# SENSE.net
KiCad netlist of a schematic drawn in Altium Designer
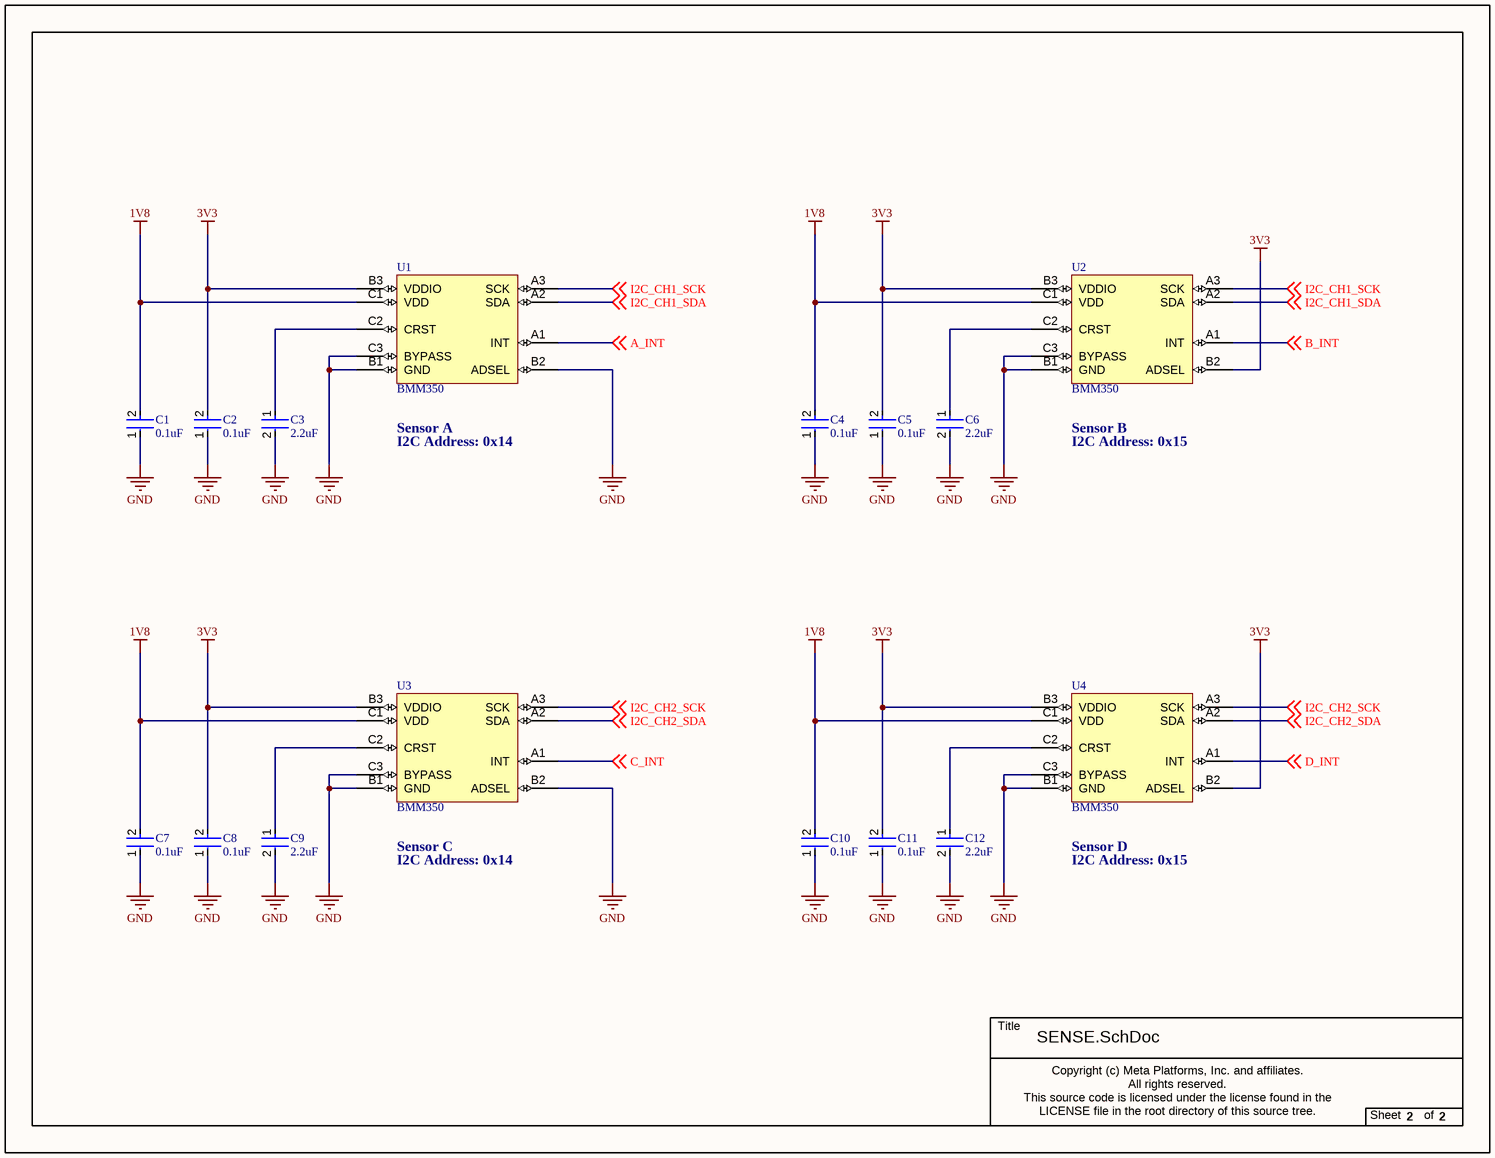
[diagram p0: SENSE.SchDoc]

(export (version "E")
  (design (tool "Eeschema 10.0.6"))
  (components
    (comp (ref "C1")
      (value "0.1uF")
      (footprint "FP-GRM15-MFG")
      (description "CAP CER 0.1UF 16V X7R 0402")
      (fields (field (name "MANUFACTURER PART NUMBER") "GRM155R71C104KA88D") (field (name "TOLERANCE") "10%"))
      (libsource (lib "Altium Content Vault") (part "236180d848d6139a670b325ea6854c9"))
    )
    (comp (ref "C2")
      (value "0.1uF")
      (footprint "FP-GRM15-MFG")
      (description "CAP CER 0.1UF 16V X7R 0402")
      (fields (field (name "MANUFACTURER PART NUMBER") "GRM155R71C104KA88D") (field (name "TOLERANCE") "10%"))
      (libsource (lib "Altium Content Vault") (part "236180d848d6139a670b325ea6854c9"))
    )
    (comp (ref "C3")
      (value "2.2uF")
      (footprint "FP-C1005-050-0_15-0_1-MFG")
      (description "CAP CER 2.2UF 10V X7S 0402")
      (fields (field (name "TOLERANCE") "10%"))
      (libsource (lib "Altium Content Vault") (part "b4654b650e69147ec39a6b967a45e02"))
    )
    (comp (ref "C4")
      (value "0.1uF")
      (footprint "FP-GRM15-MFG")
      (description "CAP CER 0.1UF 16V X7R 0402")
      (fields (field (name "MANUFACTURER PART NUMBER") "GRM155R71C104KA88D") (field (name "TOLERANCE") "10%"))
      (libsource (lib "Altium Content Vault") (part "236180d848d6139a670b325ea6854c9"))
    )
    (comp (ref "C5")
      (value "0.1uF")
      (footprint "FP-GRM15-MFG")
      (description "CAP CER 0.1UF 16V X7R 0402")
      (fields (field (name "MANUFACTURER PART NUMBER") "GRM155R71C104KA88D") (field (name "TOLERANCE") "10%"))
      (libsource (lib "Altium Content Vault") (part "236180d848d6139a670b325ea6854c9"))
    )
    (comp (ref "C6")
      (value "2.2uF")
      (footprint "FP-C1005-050-0_15-0_1-MFG")
      (description "CAP CER 2.2UF 10V X7S 0402")
      (fields (field (name "TOLERANCE") "10%"))
      (libsource (lib "Altium Content Vault") (part "b4654b650e69147ec39a6b967a45e02"))
    )
    (comp (ref "C7")
      (value "0.1uF")
      (footprint "FP-GRM15-MFG")
      (description "CAP CER 0.1UF 16V X7R 0402")
      (fields (field (name "MANUFACTURER PART NUMBER") "GRM155R71C104KA88D") (field (name "TOLERANCE") "10%"))
      (libsource (lib "Altium Content Vault") (part "236180d848d6139a670b325ea6854c9"))
    )
    (comp (ref "C8")
      (value "0.1uF")
      (footprint "FP-GRM15-MFG")
      (description "CAP CER 0.1UF 16V X7R 0402")
      (fields (field (name "MANUFACTURER PART NUMBER") "GRM155R71C104KA88D") (field (name "TOLERANCE") "10%"))
      (libsource (lib "Altium Content Vault") (part "236180d848d6139a670b325ea6854c9"))
    )
    (comp (ref "C9")
      (value "2.2uF")
      (footprint "FP-C1005-050-0_15-0_1-MFG")
      (description "CAP CER 2.2UF 10V X7S 0402")
      (fields (field (name "TOLERANCE") "10%"))
      (libsource (lib "Altium Content Vault") (part "b4654b650e69147ec39a6b967a45e02"))
    )
    (comp (ref "C10")
      (value "0.1uF")
      (footprint "FP-GRM15-MFG")
      (description "CAP CER 0.1UF 16V X7R 0402")
      (fields (field (name "MANUFACTURER PART NUMBER") "GRM155R71C104KA88D") (field (name "TOLERANCE") "10%"))
      (libsource (lib "Altium Content Vault") (part "236180d848d6139a670b325ea6854c9"))
    )
    (comp (ref "C11")
      (value "0.1uF")
      (footprint "FP-GRM15-MFG")
      (description "CAP CER 0.1UF 16V X7R 0402")
      (fields (field (name "MANUFACTURER PART NUMBER") "GRM155R71C104KA88D") (field (name "TOLERANCE") "10%"))
      (libsource (lib "Altium Content Vault") (part "236180d848d6139a670b325ea6854c9"))
    )
    (comp (ref "C12")
      (value "2.2uF")
      (footprint "FP-C1005-050-0_15-0_1-MFG")
      (description "CAP CER 2.2UF 10V X7S 0402")
      (fields (field (name "TOLERANCE") "10%"))
      (libsource (lib "Altium Content Vault") (part "b4654b650e69147ec39a6b967a45e02"))
    )
    (comp (ref "U1") (value "BMM350") (footprint "BMM350") (libsource (lib "bmm350") (part "BMM350")))
    (comp (ref "U2") (value "BMM350") (footprint "BMM350") (libsource (lib "bmm350") (part "BMM350")))
    (comp (ref "U3") (value "BMM350") (footprint "BMM350") (libsource (lib "bmm350") (part "BMM350")))
    (comp (ref "U4") (value "BMM350") (footprint "BMM350") (libsource (lib "bmm350") (part "BMM350")))
  )
  (nets
    (net (code "1") (name "1V8") (class "Default")
      (node (ref "C1") (pin "2") (pinfunction "2_2") (pintype "passive"))
      (node (ref "C10") (pin "2") (pinfunction "2_2") (pintype "passive"))
      (node (ref "C4") (pin "2") (pinfunction "2_2") (pintype "passive"))
      (node (ref "C7") (pin "2") (pinfunction "2_2") (pintype "passive"))
      (node (ref "U1") (pin "C1") (pinfunction "VDD_C1") (pintype "bidirectional"))
      (node (ref "U2") (pin "C1") (pinfunction "VDD_C1") (pintype "bidirectional"))
      (node (ref "U3") (pin "C1") (pinfunction "VDD_C1") (pintype "bidirectional"))
      (node (ref "U4") (pin "C1") (pinfunction "VDD_C1") (pintype "bidirectional"))
    )
    (net (code "2") (name "3V3") (class "Default")
      (node (ref "C11") (pin "2") (pinfunction "2_2") (pintype "passive"))
      (node (ref "C2") (pin "2") (pinfunction "2_2") (pintype "passive"))
      (node (ref "C5") (pin "2") (pinfunction "2_2") (pintype "passive"))
      (node (ref "C8") (pin "2") (pinfunction "2_2") (pintype "passive"))
      (node (ref "U1") (pin "B3") (pinfunction "VDDIO_B3") (pintype "bidirectional"))
      (node (ref "U2") (pin "B2") (pinfunction "ADSEL_B2") (pintype "bidirectional"))
      (node (ref "U2") (pin "B3") (pinfunction "VDDIO_B3") (pintype "bidirectional"))
      (node (ref "U3") (pin "B3") (pinfunction "VDDIO_B3") (pintype "bidirectional"))
      (node (ref "U4") (pin "B2") (pinfunction "ADSEL_B2") (pintype "bidirectional"))
      (node (ref "U4") (pin "B3") (pinfunction "VDDIO_B3") (pintype "bidirectional"))
    )
    (net (code "3") (name "A_INT") (class "Default")
      (node (ref "U1") (pin "A1") (pinfunction "INT_A1") (pintype "bidirectional"))
    )
    (net (code "4") (name "B_INT") (class "Default")
      (node (ref "U2") (pin "A1") (pinfunction "INT_A1") (pintype "bidirectional"))
    )
    (net (code "5") (name "C_INT") (class "Default")
      (node (ref "U3") (pin "A1") (pinfunction "INT_A1") (pintype "bidirectional"))
    )
    (net (code "6") (name "D_INT") (class "Default")
      (node (ref "U4") (pin "A1") (pinfunction "INT_A1") (pintype "bidirectional"))
    )
    (net (code "7") (name "GND") (class "Default")
      (node (ref "C1") (pin "1") (pinfunction "1_1") (pintype "passive"))
      (node (ref "C10") (pin "1") (pinfunction "1_1") (pintype "passive"))
      (node (ref "C11") (pin "1") (pinfunction "1_1") (pintype "passive"))
      (node (ref "C12") (pin "2") (pinfunction "2_2") (pintype "passive"))
      (node (ref "C2") (pin "1") (pinfunction "1_1") (pintype "passive"))
      (node (ref "C3") (pin "2") (pinfunction "2_2") (pintype "passive"))
      (node (ref "C4") (pin "1") (pinfunction "1_1") (pintype "passive"))
      (node (ref "C5") (pin "1") (pinfunction "1_1") (pintype "passive"))
      (node (ref "C6") (pin "2") (pinfunction "2_2") (pintype "passive"))
      (node (ref "C7") (pin "1") (pinfunction "1_1") (pintype "passive"))
      (node (ref "C8") (pin "1") (pinfunction "1_1") (pintype "passive"))
      (node (ref "C9") (pin "2") (pinfunction "2_2") (pintype "passive"))
      (node (ref "U1") (pin "B1") (pinfunction "GND_B1") (pintype "bidirectional"))
      (node (ref "U1") (pin "B2") (pinfunction "ADSEL_B2") (pintype "bidirectional"))
      (node (ref "U1") (pin "C3") (pinfunction "BYPASS_C3") (pintype "bidirectional"))
      (node (ref "U2") (pin "B1") (pinfunction "GND_B1") (pintype "bidirectional"))
      (node (ref "U2") (pin "C3") (pinfunction "BYPASS_C3") (pintype "bidirectional"))
      (node (ref "U3") (pin "B1") (pinfunction "GND_B1") (pintype "bidirectional"))
      (node (ref "U3") (pin "B2") (pinfunction "ADSEL_B2") (pintype "bidirectional"))
      (node (ref "U3") (pin "C3") (pinfunction "BYPASS_C3") (pintype "bidirectional"))
      (node (ref "U4") (pin "B1") (pinfunction "GND_B1") (pintype "bidirectional"))
      (node (ref "U4") (pin "C3") (pinfunction "BYPASS_C3") (pintype "bidirectional"))
    )
    (net (code "8") (name "I2C_CH1_SCK") (class "Default")
      (node (ref "U1") (pin "A3") (pinfunction "SCK_A3") (pintype "bidirectional"))
      (node (ref "U2") (pin "A3") (pinfunction "SCK_A3") (pintype "bidirectional"))
    )
    (net (code "9") (name "I2C_CH1_SDA") (class "Default")
      (node (ref "U1") (pin "A2") (pinfunction "SDA_A2") (pintype "bidirectional"))
      (node (ref "U2") (pin "A2") (pinfunction "SDA_A2") (pintype "bidirectional"))
    )
    (net (code "10") (name "I2C_CH2_SCK") (class "Default")
      (node (ref "U3") (pin "A3") (pinfunction "SCK_A3") (pintype "bidirectional"))
      (node (ref "U4") (pin "A3") (pinfunction "SCK_A3") (pintype "bidirectional"))
    )
    (net (code "11") (name "I2C_CH2_SDA") (class "Default")
      (node (ref "U3") (pin "A2") (pinfunction "SDA_A2") (pintype "bidirectional"))
      (node (ref "U4") (pin "A2") (pinfunction "SDA_A2") (pintype "bidirectional"))
    )
    (net (code "12") (name "Net-(U1-CRST)") (class "Default")
      (node (ref "C3") (pin "1") (pinfunction "1_1") (pintype "passive"))
      (node (ref "U1") (pin "C2") (pinfunction "CRST_C2") (pintype "bidirectional"))
    )
    (net (code "13") (name "Net-(U2-CRST)") (class "Default")
      (node (ref "C6") (pin "1") (pinfunction "1_1") (pintype "passive"))
      (node (ref "U2") (pin "C2") (pinfunction "CRST_C2") (pintype "bidirectional"))
    )
    (net (code "14") (name "Net-(U3-CRST)") (class "Default")
      (node (ref "C9") (pin "1") (pinfunction "1_1") (pintype "passive"))
      (node (ref "U3") (pin "C2") (pinfunction "CRST_C2") (pintype "bidirectional"))
    )
    (net (code "15") (name "Net-(U4-CRST)") (class "Default")
      (node (ref "C12") (pin "1") (pinfunction "1_1") (pintype "passive"))
      (node (ref "U4") (pin "C2") (pinfunction "CRST_C2") (pintype "bidirectional"))
    )
  )
)
